# Buggy_Motor_Board.net
KiCad netlist of a schematic drawn in EAGLE
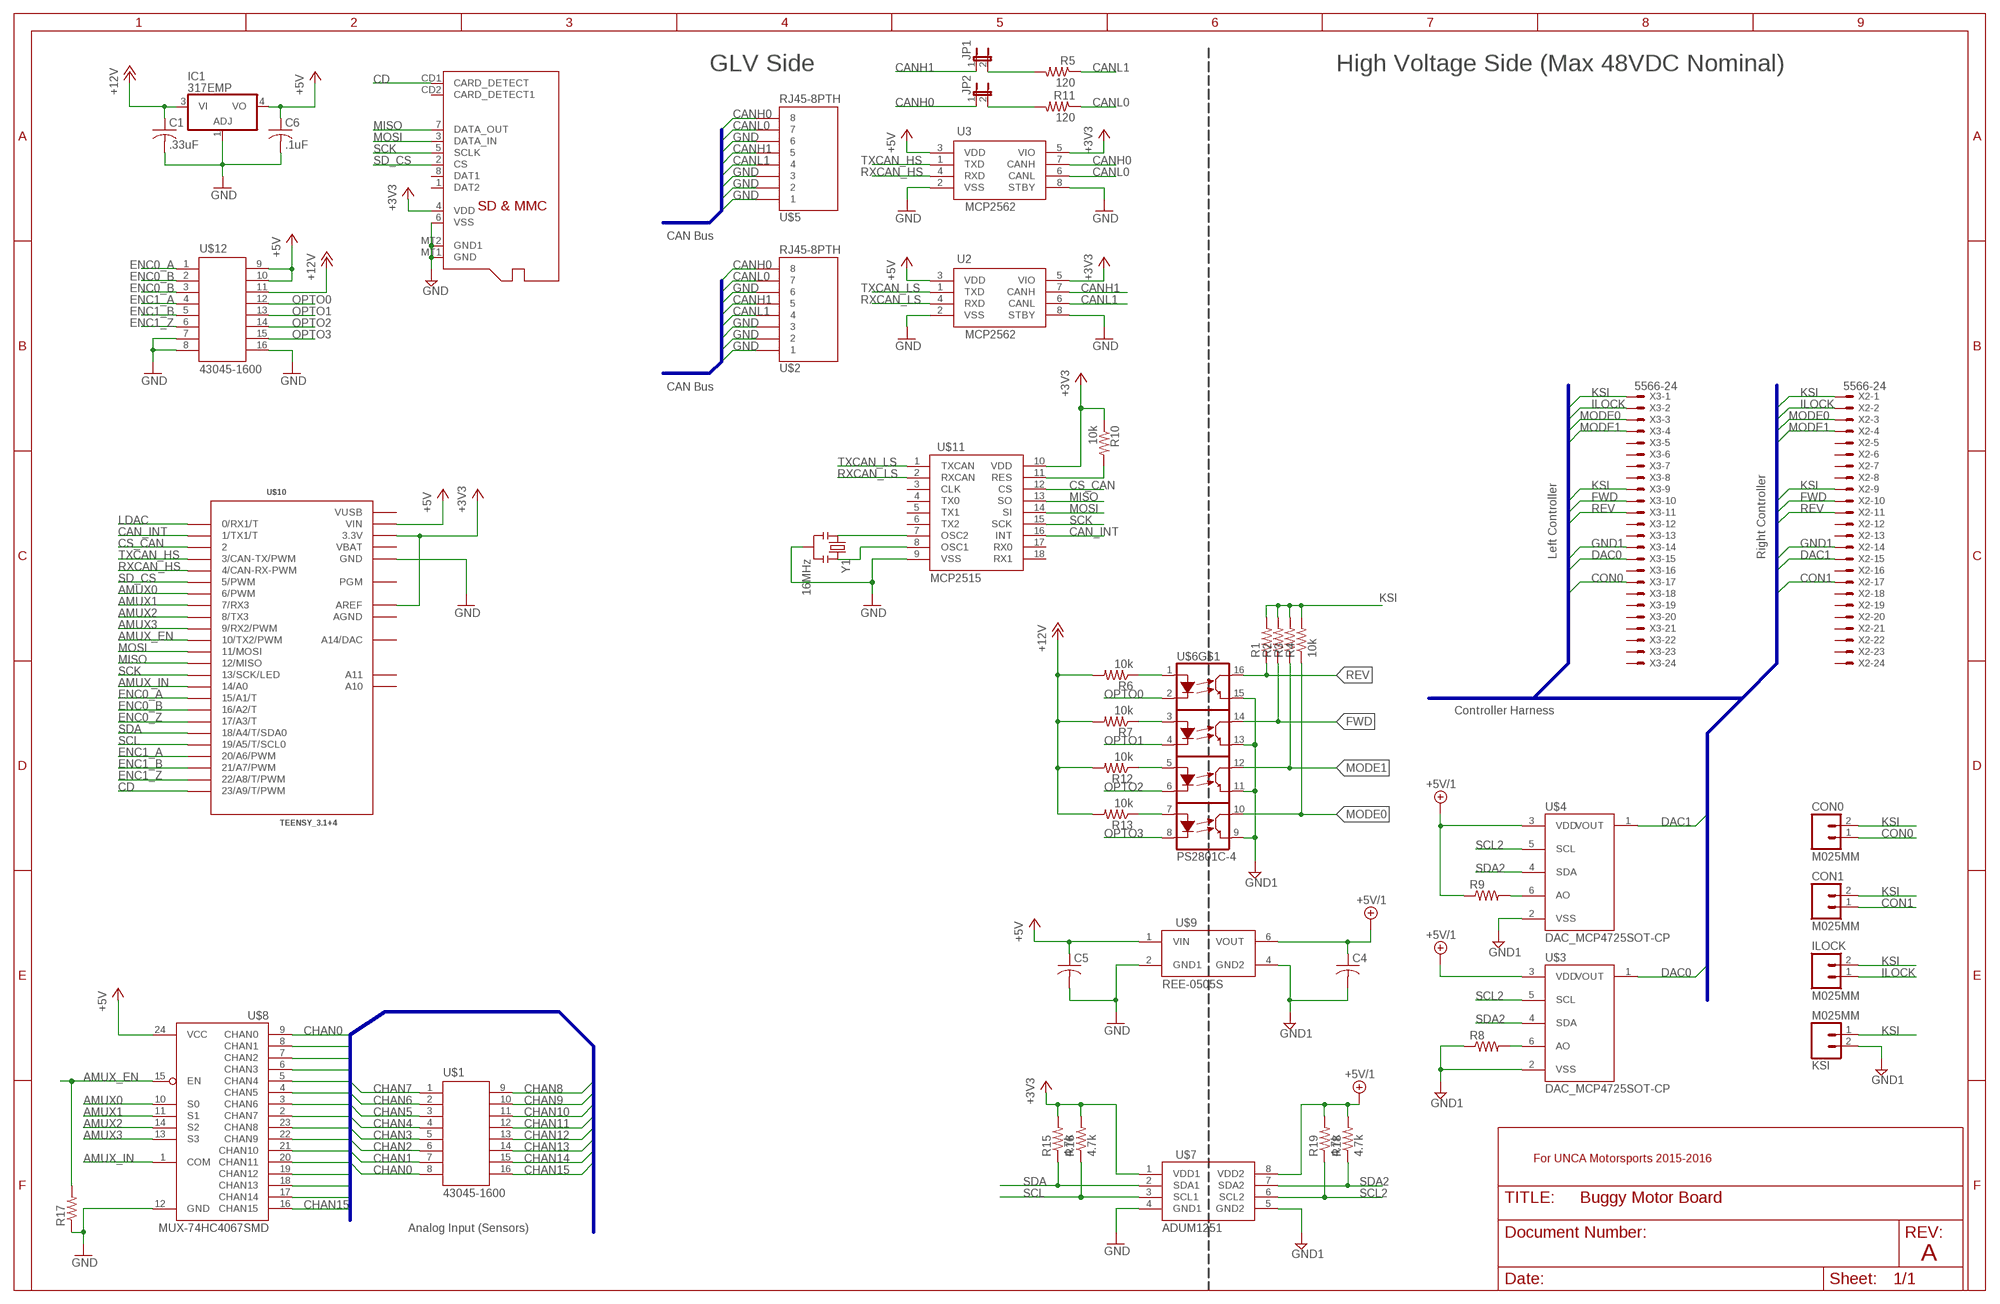
[diagram p0: schematic, sheet 1]

(export (version "E")
  (design (tool "Eeschema 10.0.6"))
  (components
    (comp (ref "C1")
      (value ".33uF")
      (footprint "eagle-import:C0805")
      (libsource (lib "eagle-import") (part "C-USC0805"))
    )
    (comp (ref "C4")
      (value "C-USC1210K")
      (footprint "eagle-import:C1210K")
      (libsource (lib "eagle-import") (part "C-USC1210K"))
    )
    (comp (ref "C5")
      (value "C-USC1210K")
      (footprint "eagle-import:C1210K")
      (libsource (lib "eagle-import") (part "C-USC1210K"))
    )
    (comp (ref "C6")
      (value ".1uF")
      (footprint "eagle-import:C0805")
      (libsource (lib "eagle-import") (part "C-USC0805"))
    )
    (comp (ref "CON0")
      (value "M025MM")
      (footprint "eagle-import:SCREWTERMINAL-5MM-2")
      (libsource (lib "eagle-import") (part "M025MM"))
    )
    (comp (ref "CON1")
      (value "M025MM")
      (footprint "eagle-import:SCREWTERMINAL-5MM-2")
      (libsource (lib "eagle-import") (part "M025MM"))
    )
    (comp (ref "IC1")
      (value "317EMP")
      (footprint "eagle-import:SOT223")
      (libsource (lib "eagle-import") (part "317EMP"))
    )
    (comp (ref "ILOCK")
      (value "M025MM")
      (footprint "eagle-import:SCREWTERMINAL-5MM-2")
      (libsource (lib "eagle-import") (part "M025MM"))
    )
    (comp (ref "JP1")
      (value "JP1E")
      (footprint "eagle-import:JP1")
      (libsource (lib "eagle-import") (part "JP1E"))
    )
    (comp (ref "JP2")
      (value "JP1E")
      (footprint "eagle-import:JP1")
      (libsource (lib "eagle-import") (part "JP1E"))
    )
    (comp (ref "KSI")
      (value "M025MM")
      (footprint "eagle-import:SCREWTERMINAL-5MM-2")
      (libsource (lib "eagle-import") (part "M025MM"))
    )
    (comp (ref "R1")
      (value "RESISTOR0805-RES")
      (footprint "eagle-import:0805")
      (libsource (lib "eagle-import") (part "RESISTOR0805-RES"))
    )
    (comp (ref "R2")
      (value "RESISTOR0805-RES")
      (footprint "eagle-import:0805")
      (libsource (lib "eagle-import") (part "RESISTOR0805-RES"))
    )
    (comp (ref "R3")
      (value "RESISTOR0805-RES")
      (footprint "eagle-import:0805")
      (libsource (lib "eagle-import") (part "RESISTOR0805-RES"))
    )
    (comp (ref "R4")
      (value "10k")
      (footprint "eagle-import:0805")
      (libsource (lib "eagle-import") (part "RESISTOR0805-RES"))
    )
    (comp (ref "R5")
      (value "120")
      (footprint "eagle-import:0805")
      (libsource (lib "eagle-import") (part "RESISTOR0805-RES"))
    )
    (comp (ref "R6")
      (value "10k")
      (footprint "eagle-import:0805")
      (libsource (lib "eagle-import") (part "RESISTOR0805-RES"))
    )
    (comp (ref "R7")
      (value "10k")
      (footprint "eagle-import:0805")
      (libsource (lib "eagle-import") (part "RESISTOR0805-RES"))
    )
    (comp (ref "R8")
      (value "RESISTOR0805-RES")
      (footprint "eagle-import:0805")
      (libsource (lib "eagle-import") (part "RESISTOR0805-RES"))
    )
    (comp (ref "R9")
      (value "RESISTOR0805-RES")
      (footprint "eagle-import:0805")
      (libsource (lib "eagle-import") (part "RESISTOR0805-RES"))
    )
    (comp (ref "R10")
      (value "10k")
      (footprint "eagle-import:0805")
      (libsource (lib "eagle-import") (part "RESISTOR0805-RES"))
    )
    (comp (ref "R11")
      (value "120")
      (footprint "eagle-import:0805")
      (libsource (lib "eagle-import") (part "RESISTOR0805-RES"))
    )
    (comp (ref "R12")
      (value "10k")
      (footprint "eagle-import:0805")
      (libsource (lib "eagle-import") (part "RESISTOR0805-RES"))
    )
    (comp (ref "R13")
      (value "10k")
      (footprint "eagle-import:0805")
      (libsource (lib "eagle-import") (part "RESISTOR0805-RES"))
    )
    (comp (ref "R15")
      (value "4.7k")
      (footprint "eagle-import:0805")
      (libsource (lib "eagle-import") (part "RESISTOR0805-RES"))
    )
    (comp (ref "R16")
      (value "4.7k")
      (footprint "eagle-import:0805")
      (libsource (lib "eagle-import") (part "RESISTOR0805-RES"))
    )
    (comp (ref "R17")
      (value "RESISTOR0805-RES")
      (footprint "eagle-import:0805")
      (libsource (lib "eagle-import") (part "RESISTOR0805-RES"))
    )
    (comp (ref "R18")
      (value "4.7k")
      (footprint "eagle-import:0805")
      (libsource (lib "eagle-import") (part "RESISTOR0805-RES"))
    )
    (comp (ref "R19")
      (value "4.7k")
      (footprint "eagle-import:0805")
      (libsource (lib "eagle-import") (part "RESISTOR0805-RES"))
    )
    (comp (ref "U$1")
      (value "43045-1600")
      (footprint "eagle-import:43045-1600")
      (libsource (lib "eagle-import") (part "43045-1600"))
    )
    (comp (ref "U$2")
      (value "RJ45-8PTH")
      (footprint "eagle-import:RJ45-8")
      (libsource (lib "eagle-import") (part "RJ45-8PTH"))
    )
    (comp (ref "U$3")
      (value "DAC_MCP4725SOT-CP")
      (footprint "eagle-import:SOT23-6-MCP4725")
      (libsource (lib "eagle-import") (part "DAC_MCP4725SOT-CP"))
    )
    (comp (ref "U$4")
      (value "DAC_MCP4725SOT-CP")
      (footprint "eagle-import:SOT23-6-MCP4725")
      (libsource (lib "eagle-import") (part "DAC_MCP4725SOT-CP"))
    )
    (comp (ref "U$5")
      (value "RJ45-8PTH")
      (footprint "eagle-import:RJ45-8")
      (libsource (lib "eagle-import") (part "RJ45-8PTH"))
    )
    (comp (ref "U$6")
      (value "PS2801C-4")
      (footprint "eagle-import:16-SOIC")
      (libsource (lib "eagle-import") (part "PS2801C-4"))
    )
    (comp (ref "U$7")
      (value "ADUM1251")
      (footprint "eagle-import:8-SOIC")
      (libsource (lib "eagle-import") (part "ADUM1251"))
    )
    (comp (ref "U$8")
      (value "MUX-74HC4067SMD")
      (footprint "eagle-import:SSOP24")
      (libsource (lib "eagle-import") (part "MUX-74HC4067SMD"))
    )
    (comp (ref "U$9")
      (value "REE-0505S")
      (footprint "eagle-import:REE-0505S")
      (libsource (lib "eagle-import") (part "REE-0505S"))
    )
    (comp (ref "U$10")
      (value "TEENSY_3.1+4")
      (footprint "eagle-import:TEENSY_3.1+4")
      (libsource (lib "eagle-import") (part "TEENSY_3.1+4"))
    )
    (comp (ref "U$11")
      (value "MCP2515")
      (footprint "eagle-import:DIL18")
      (libsource (lib "eagle-import") (part "MCP2515"))
    )
    (comp (ref "U$12")
      (value "43045-1600")
      (footprint "eagle-import:43045-1600")
      (libsource (lib "eagle-import") (part "43045-1600"))
    )
    (comp (ref "U2")
      (value "MCP2562")
      (footprint "eagle-import:SO08")
      (libsource (lib "eagle-import") (part "MCP2562"))
    )
    (comp (ref "U3")
      (value "MCP2562")
      (footprint "eagle-import:SO08")
      (libsource (lib "eagle-import") (part "MCP2562"))
    )
    (comp (ref "X1")
      (value "MICROSD")
      (footprint "eagle-import:MICROSD")
      (libsource (lib "eagle-import") (part "MICROSD"))
    )
    (comp (ref "X2")
      (value "5566-24")
      (footprint "eagle-import:5566-24")
      (libsource (lib "eagle-import") (part "5566-24"))
    )
    (comp (ref "X3")
      (value "5566-24")
      (footprint "eagle-import:5566-24")
      (libsource (lib "eagle-import") (part "5566-24"))
    )
    (comp (ref "Y1")
      (value "16MHz")
      (footprint "eagle-import:RESONATOR-PTH")
      (libsource (lib "eagle-import") (part "RESONATORPTH"))
    )
  )
  (nets
    (net (code "5") (name "+3V3") (class "Default")
      (node (ref "R10") (pin "1") (pinfunction "1_1") (pintype "passive"))
      (node (ref "R15") (pin "2") (pinfunction "2_2") (pintype "passive"))
      (node (ref "R16") (pin "2") (pinfunction "2_2") (pintype "passive"))
      (node (ref "U$10") (pin "3.3V") (pinfunction "3.3V_3.3V") (pintype "power_in"))
      (node (ref "U$10") (pin "3.3V1") (pinfunction "3.3V_3.3V1") (pintype "power_in"))
      (node (ref "U$10") (pin "AREF") (pinfunction "AREF_AREF") (pintype "power_in"))
      (node (ref "U$11") (pin "10") (pinfunction "VDD_10") (pintype "bidirectional"))
      (node (ref "U$7") (pin "1") (pinfunction "VDD1_1") (pintype "bidirectional"))
      (node (ref "U2") (pin "5") (pinfunction "VIO_5") (pintype "bidirectional"))
      (node (ref "U3") (pin "5") (pinfunction "VIO_5") (pintype "bidirectional"))
      (node (ref "X1") (pin "4") (pinfunction "VDD_4") (pintype "power_in"))
    )
    (net (code "6") (name "+5V") (class "Default")
      (node (ref "C5") (pin "1") (pinfunction "1_1") (pintype "passive"))
      (node (ref "C6") (pin "1") (pinfunction "1_1") (pintype "passive"))
      (node (ref "IC1") (pin "4") (pinfunction "VO_4") (pintype "passive"))
      (node (ref "U$10") (pin "VIN") (pinfunction "VIN_VIN") (pintype "power_in"))
      (node (ref "U$12") (pin "10") (pinfunction "P$10_10") (pintype "passive"))
      (node (ref "U$12") (pin "9") (pinfunction "P$9_9") (pintype "passive"))
      (node (ref "U$8") (pin "24") (pinfunction "VCC_24") (pintype "bidirectional"))
      (node (ref "U$9") (pin "1") (pinfunction "VIN_1") (pintype "bidirectional"))
      (node (ref "U2") (pin "3") (pinfunction "VDD_3") (pintype "bidirectional"))
      (node (ref "U3") (pin "3") (pinfunction "VDD_3") (pintype "bidirectional"))
    )
    (net (code "7") (name "+5V{slash}1") (class "Default")
      (node (ref "C4") (pin "1") (pinfunction "1_1") (pintype "passive"))
      (node (ref "R18") (pin "2") (pinfunction "2_2") (pintype "passive"))
      (node (ref "R19") (pin "2") (pinfunction "2_2") (pintype "passive"))
      (node (ref "R9") (pin "1") (pinfunction "1_1") (pintype "passive"))
      (node (ref "U$3") (pin "3") (pinfunction "VDD_3") (pintype "bidirectional"))
      (node (ref "U$4") (pin "3") (pinfunction "VDD_3") (pintype "bidirectional"))
      (node (ref "U$7") (pin "8") (pinfunction "VDD2_8") (pintype "bidirectional"))
      (node (ref "U$9") (pin "6") (pinfunction "VOUT_6") (pintype "bidirectional"))
    )
    (net (code "8") (name "+12V") (class "Default")
      (node (ref "C1") (pin "1") (pinfunction "1_1") (pintype "passive"))
      (node (ref "IC1") (pin "3") (pinfunction "VI_3") (pintype "input"))
      (node (ref "R12") (pin "2") (pinfunction "2_2") (pintype "passive"))
      (node (ref "R13") (pin "2") (pinfunction "2_2") (pintype "passive"))
      (node (ref "R6") (pin "2") (pinfunction "2_2") (pintype "passive"))
      (node (ref "R7") (pin "2") (pinfunction "2_2") (pintype "passive"))
      (node (ref "U$12") (pin "11") (pinfunction "P$11_11") (pintype "passive"))
    )
    (net (code "9") (name "/AGND") (class "Default")
      (node (ref "U$10") (pin "AGND") (pinfunction "AGND_AGND") (pintype "power_in"))
    )
    (net (code "10") (name "/AMUX0") (class "Default")
      (node (ref "U$10") (pin "6") (pinfunction "6/PWM_6") (pintype "bidirectional"))
      (node (ref "U$8") (pin "10") (pinfunction "S0_10") (pintype "input"))
    )
    (net (code "11") (name "/AMUX1") (class "Default")
      (node (ref "U$10") (pin "7") (pinfunction "7/RX3_7") (pintype "bidirectional"))
      (node (ref "U$8") (pin "11") (pinfunction "S1_11") (pintype "input"))
    )
    (net (code "12") (name "/AMUX2") (class "Default")
      (node (ref "U$10") (pin "8") (pinfunction "8/TX3_8") (pintype "bidirectional"))
      (node (ref "U$8") (pin "14") (pinfunction "S2_14") (pintype "input"))
    )
    (net (code "13") (name "/AMUX3") (class "Default")
      (node (ref "U$10") (pin "9") (pinfunction "9/RX2/PWM_9") (pintype "bidirectional"))
      (node (ref "U$8") (pin "13") (pinfunction "S3_13") (pintype "input"))
    )
    (net (code "14") (name "/AMUX_EN") (class "Default")
      (node (ref "R17") (pin "2") (pinfunction "2_2") (pintype "passive"))
      (node (ref "U$10") (pin "10") (pinfunction "10/TX2/PWM_10") (pintype "bidirectional"))
      (node (ref "U$8") (pin "15") (pinfunction "EN_15") (pintype "input"))
    )
    (net (code "15") (name "/AMUX_IN") (class "Default")
      (node (ref "U$10") (pin "14/A0") (pinfunction "14/A0_14/A0") (pintype "bidirectional"))
      (node (ref "U$8") (pin "1") (pinfunction "COM_1") (pintype "bidirectional"))
    )
    (net (code "16") (name "/CANH0") (class "Default")
      (node (ref "JP2") (pin "1") (pinfunction "1_1") (pintype "passive"))
      (node (ref "U$2") (pin "8") (pinfunction "8_8") (pintype "bidirectional"))
      (node (ref "U$5") (pin "8") (pinfunction "8_8") (pintype "bidirectional"))
      (node (ref "U3") (pin "7") (pinfunction "CANH_7") (pintype "bidirectional"))
    )
    (net (code "17") (name "/CANH1") (class "Default")
      (node (ref "JP1") (pin "1") (pinfunction "1_1") (pintype "passive"))
      (node (ref "U$2") (pin "5") (pinfunction "5_5") (pintype "bidirectional"))
      (node (ref "U$5") (pin "5") (pinfunction "5_5") (pintype "bidirectional"))
      (node (ref "U2") (pin "7") (pinfunction "CANH_7") (pintype "bidirectional"))
    )
    (net (code "18") (name "/CANL0") (class "Default")
      (node (ref "R11") (pin "1") (pinfunction "1_1") (pintype "passive"))
      (node (ref "U$2") (pin "7") (pinfunction "7_7") (pintype "bidirectional"))
      (node (ref "U$5") (pin "7") (pinfunction "7_7") (pintype "bidirectional"))
      (node (ref "U3") (pin "6") (pinfunction "CANL_6") (pintype "bidirectional"))
    )
    (net (code "19") (name "/CANL1") (class "Default")
      (node (ref "R5") (pin "1") (pinfunction "1_1") (pintype "passive"))
      (node (ref "U$2") (pin "4") (pinfunction "4_4") (pintype "bidirectional"))
      (node (ref "U$5") (pin "4") (pinfunction "4_4") (pintype "bidirectional"))
      (node (ref "U2") (pin "6") (pinfunction "CANL_6") (pintype "bidirectional"))
    )
    (net (code "20") (name "/CAN_INT") (class "Default")
      (node (ref "U$10") (pin "1") (pinfunction "1/TX1/T_1") (pintype "bidirectional"))
      (node (ref "U$11") (pin "16") (pinfunction "INT_16") (pintype "bidirectional"))
    )
    (net (code "21") (name "/CD") (class "Default")
      (node (ref "U$10") (pin "23/A9") (pinfunction "23/A9/T/PWM_23/A9") (pintype "bidirectional"))
      (node (ref "X1") (pin "CD1") (pinfunction "CARD_DETECT_CD1") (pintype "passive"))
    )
    (net (code "22") (name "/CHAN0") (class "Default")
      (node (ref "U$1") (pin "8") (pinfunction "P$8_8") (pintype "passive"))
      (node (ref "U$8") (pin "9") (pinfunction "CHAN0_9") (pintype "bidirectional"))
    )
    (net (code "23") (name "/CHAN1") (class "Default")
      (node (ref "U$1") (pin "7") (pinfunction "P$7_7") (pintype "passive"))
      (node (ref "U$8") (pin "8") (pinfunction "CHAN1_8") (pintype "bidirectional"))
    )
    (net (code "24") (name "/CHAN2") (class "Default")
      (node (ref "U$1") (pin "6") (pinfunction "P$6_6") (pintype "passive"))
      (node (ref "U$8") (pin "7") (pinfunction "CHAN2_7") (pintype "bidirectional"))
    )
    (net (code "25") (name "/CHAN3") (class "Default")
      (node (ref "U$1") (pin "5") (pinfunction "P$5_5") (pintype "passive"))
      (node (ref "U$8") (pin "6") (pinfunction "CHAN3_6") (pintype "bidirectional"))
    )
    (net (code "26") (name "/CHAN4") (class "Default")
      (node (ref "U$1") (pin "4") (pinfunction "P$4_4") (pintype "passive"))
      (node (ref "U$8") (pin "5") (pinfunction "CHAN4_5") (pintype "bidirectional"))
    )
    (net (code "27") (name "/CHAN5") (class "Default")
      (node (ref "U$1") (pin "3") (pinfunction "P$3_3") (pintype "passive"))
      (node (ref "U$8") (pin "4") (pinfunction "CHAN5_4") (pintype "bidirectional"))
    )
    (net (code "28") (name "/CHAN6") (class "Default")
      (node (ref "U$1") (pin "2") (pinfunction "P$2_2") (pintype "passive"))
      (node (ref "U$8") (pin "3") (pinfunction "CHAN6_3") (pintype "bidirectional"))
    )
    (net (code "29") (name "/CHAN7") (class "Default")
      (node (ref "U$1") (pin "1") (pinfunction "P$1_1") (pintype "passive"))
      (node (ref "U$8") (pin "2") (pinfunction "CHAN7_2") (pintype "bidirectional"))
    )
    (net (code "30") (name "/CHAN8") (class "Default")
      (node (ref "U$1") (pin "9") (pinfunction "P$9_9") (pintype "passive"))
      (node (ref "U$8") (pin "23") (pinfunction "CHAN8_23") (pintype "bidirectional"))
    )
    (net (code "31") (name "/CHAN9") (class "Default")
      (node (ref "U$1") (pin "10") (pinfunction "P$10_10") (pintype "passive"))
      (node (ref "U$8") (pin "22") (pinfunction "CHAN9_22") (pintype "bidirectional"))
    )
    (net (code "32") (name "/CHAN10") (class "Default")
      (node (ref "U$1") (pin "11") (pinfunction "P$11_11") (pintype "passive"))
      (node (ref "U$8") (pin "21") (pinfunction "CHAN10_21") (pintype "bidirectional"))
    )
    (net (code "33") (name "/CHAN11") (class "Default")
      (node (ref "U$1") (pin "12") (pinfunction "P$12_12") (pintype "passive"))
      (node (ref "U$8") (pin "20") (pinfunction "CHAN11_20") (pintype "bidirectional"))
    )
    (net (code "34") (name "/CHAN12") (class "Default")
      (node (ref "U$1") (pin "13") (pinfunction "P$13_13") (pintype "passive"))
      (node (ref "U$8") (pin "19") (pinfunction "CHAN12_19") (pintype "bidirectional"))
    )
    (net (code "35") (name "/CHAN13") (class "Default")
      (node (ref "U$1") (pin "14") (pinfunction "P$14_14") (pintype "passive"))
      (node (ref "U$8") (pin "18") (pinfunction "CHAN13_18") (pintype "bidirectional"))
    )
    (net (code "36") (name "/CHAN14") (class "Default")
      (node (ref "U$1") (pin "15") (pinfunction "P$15_15") (pintype "passive"))
      (node (ref "U$8") (pin "17") (pinfunction "CHAN14_17") (pintype "bidirectional"))
    )
    (net (code "37") (name "/CHAN15") (class "Default")
      (node (ref "U$1") (pin "16") (pinfunction "P$16_16") (pintype "passive"))
      (node (ref "U$8") (pin "16") (pinfunction "CHAN15_16") (pintype "bidirectional"))
    )
    (net (code "38") (name "/CON0") (class "Default")
      (node (ref "CON0") (pin "1") (pinfunction "1_1") (pintype "passive"))
      (node (ref "X3") (pin "17") (pinfunction "S_17") (pintype "passive"))
    )
    (net (code "39") (name "/CON1") (class "Default")
      (node (ref "CON1") (pin "1") (pinfunction "1_1") (pintype "passive"))
      (node (ref "X2") (pin "17") (pinfunction "S_17") (pintype "passive"))
    )
    (net (code "40") (name "/CS_CAN") (class "Default")
      (node (ref "U$10") (pin "2") (pinfunction "2_2") (pintype "bidirectional"))
      (node (ref "U$11") (pin "12") (pinfunction "CS_12") (pintype "bidirectional"))
    )
    (net (code "41") (name "/DAC0") (class "Default")
      (node (ref "U$3") (pin "1") (pinfunction "VOUT_1") (pintype "bidirectional"))
      (node (ref "X3") (pin "15") (pinfunction "S_15") (pintype "passive"))
    )
    (net (code "42") (name "/DAC1") (class "Default")
      (node (ref "U$4") (pin "1") (pinfunction "VOUT_1") (pintype "bidirectional"))
      (node (ref "X2") (pin "15") (pinfunction "S_15") (pintype "passive"))
    )
    (net (code "43") (name "/ENC0_A") (class "Default")
      (node (ref "U$10") (pin "15/A1") (pinfunction "15/A1/T_15/A1") (pintype "bidirectional"))
      (node (ref "U$12") (pin "1") (pinfunction "P$1_1") (pintype "passive"))
    )
    (net (code "44") (name "/ENC0_B") (class "Default")
      (node (ref "U$10") (pin "16/A2") (pinfunction "16/A2/T_16/A2") (pintype "bidirectional"))
      (node (ref "U$12") (pin "2") (pinfunction "P$2_2") (pintype "passive"))
    )
    (net (code "45") (name "/ENC0_Z") (class "Default")
      (node (ref "U$10") (pin "17/A3") (pinfunction "17/A3/T_17/A3") (pintype "bidirectional"))
      (node (ref "U$12") (pin "3") (pinfunction "P$3_3") (pintype "passive"))
    )
    (net (code "46") (name "/ENC1_A") (class "Default")
      (node (ref "U$10") (pin "20/A6") (pinfunction "20/A6/PWM_20/A6") (pintype "bidirectional"))
      (node (ref "U$12") (pin "4") (pinfunction "P$4_4") (pintype "passive"))
    )
    (net (code "47") (name "/ENC1_B") (class "Default")
      (node (ref "U$10") (pin "21/A7") (pinfunction "21/A7/PWM_21/A7") (pintype "bidirectional"))
      (node (ref "U$12") (pin "5") (pinfunction "P$5_5") (pintype "passive"))
    )
    (net (code "48") (name "/ENC1_Z") (class "Default")
      (node (ref "U$10") (pin "22/A8") (pinfunction "22/A8/T/PWM_22/A8") (pintype "bidirectional"))
      (node (ref "U$12") (pin "6") (pinfunction "P$6_6") (pintype "passive"))
    )
    (net (code "49") (name "/ILOCK") (class "Default")
      (node (ref "ILOCK") (pin "1") (pinfunction "1_1") (pintype "passive"))
      (node (ref "X2") (pin "2") (pinfunction "S_2") (pintype "passive"))
      (node (ref "X3") (pin "2") (pinfunction "S_2") (pintype "passive"))
    )
    (net (code "50") (name "/KSI") (class "Default")
      (node (ref "CON0") (pin "2") (pinfunction "2_2") (pintype "passive"))
      (node (ref "CON1") (pin "2") (pinfunction "2_2") (pintype "passive"))
      (node (ref "ILOCK") (pin "2") (pinfunction "2_2") (pintype "passive"))
      (node (ref "KSI") (pin "1") (pinfunction "1_1") (pintype "passive"))
      (node (ref "R1") (pin "2") (pinfunction "2_2") (pintype "passive"))
      (node (ref "R2") (pin "2") (pinfunction "2_2") (pintype "passive"))
      (node (ref "R3") (pin "2") (pinfunction "2_2") (pintype "passive"))
      (node (ref "R4") (pin "2") (pinfunction "2_2") (pintype "passive"))
      (node (ref "X2") (pin "1") (pinfunction "S_1") (pintype "passive"))
      (node (ref "X2") (pin "9") (pinfunction "S_9") (pintype "passive"))
      (node (ref "X3") (pin "1") (pinfunction "S_1") (pintype "passive"))
      (node (ref "X3") (pin "9") (pinfunction "S_9") (pintype "passive"))
    )
    (net (code "51") (name "/LDAC") (class "Default")
      (node (ref "U$10") (pin "0") (pinfunction "0/RX1/T_0") (pintype "bidirectional"))
    )
    (net (code "52") (name "/MISO") (class "Default")
      (node (ref "U$10") (pin "12") (pinfunction "12/MISO_12") (pintype "bidirectional"))
      (node (ref "U$11") (pin "13") (pinfunction "SO_13") (pintype "bidirectional"))
      (node (ref "X1") (pin "7") (pinfunction "DATA_OUT_7") (pintype "output"))
    )
    (net (code "53") (name "/MOSI") (class "Default")
      (node (ref "U$10") (pin "11") (pinfunction "11/MOSI_11") (pintype "bidirectional"))
      (node (ref "U$11") (pin "14") (pinfunction "SI_14") (pintype "bidirectional"))
      (node (ref "X1") (pin "3") (pinfunction "DATA_IN_3") (pintype "input"))
    )
    (net (code "54") (name "/OPTO0") (class "Default")
      (node (ref "U$12") (pin "12") (pinfunction "P$12_12") (pintype "passive"))
      (node (ref "U$6") (pin "2") (pinfunction "C_2") (pintype "passive"))
    )
    (net (code "55") (name "/OPTO1") (class "Default")
      (node (ref "U$12") (pin "13") (pinfunction "P$13_13") (pintype "passive"))
      (node (ref "U$6") (pin "4") (pinfunction "C_4") (pintype "passive"))
    )
    (net (code "56") (name "/OPTO2") (class "Default")
      (node (ref "U$12") (pin "14") (pinfunction "P$14_14") (pintype "passive"))
      (node (ref "U$6") (pin "6") (pinfunction "C_6") (pintype "passive"))
    )
    (net (code "57") (name "/OPTO3") (class "Default")
      (node (ref "U$12") (pin "15") (pinfunction "P$15_15") (pintype "passive"))
      (node (ref "U$6") (pin "8") (pinfunction "C_8") (pintype "passive"))
    )
    (net (code "58") (name "/RXCAN_HS") (class "Default")
      (node (ref "U$10") (pin "4") (pinfunction "4/CAN-RX-PWM_4") (pintype "bidirectional"))
      (node (ref "U3") (pin "4") (pinfunction "RXD_4") (pintype "bidirectional"))
    )
    (net (code "59") (name "/RXCAN_LS") (class "Default")
      (node (ref "U$11") (pin "2") (pinfunction "RXCAN_2") (pintype "bidirectional"))
      (node (ref "U2") (pin "4") (pinfunction "RXD_4") (pintype "bidirectional"))
    )
    (net (code "60") (name "/SCK") (class "Default")
      (node (ref "U$10") (pin "13") (pinfunction "13/SCK/LED_13") (pintype "bidirectional"))
      (node (ref "U$11") (pin "15") (pinfunction "SCK_15") (pintype "bidirectional"))
      (node (ref "X1") (pin "5") (pinfunction "SCLK_5") (pintype "input"))
    )
    (net (code "61") (name "/SCL") (class "Default")
      (node (ref "R16") (pin "1") (pinfunction "1_1") (pintype "passive"))
      (node (ref "U$10") (pin "19/A5") (pinfunction "19/A5/T/SCL0_19/A5") (pintype "bidirectional"))
      (node (ref "U$7") (pin "3") (pinfunction "SCL1_3") (pintype "bidirectional"))
    )
    (net (code "62") (name "/SCL2") (class "Default")
      (node (ref "R19") (pin "1") (pinfunction "1_1") (pintype "passive"))
      (node (ref "U$3") (pin "5") (pinfunction "SCL_5") (pintype "bidirectional"))
      (node (ref "U$4") (pin "5") (pinfunction "SCL_5") (pintype "bidirectional"))
      (node (ref "U$7") (pin "6") (pinfunction "SCL2_6") (pintype "bidirectional"))
    )
    (net (code "63") (name "/SDA") (class "Default")
      (node (ref "R15") (pin "1") (pinfunction "1_1") (pintype "passive"))
      (node (ref "U$10") (pin "18/A4") (pinfunction "18/A4/T/SDA0_18/A4") (pintype "bidirectional"))
      (node (ref "U$7") (pin "2") (pinfunction "SDA1_2") (pintype "bidirectional"))
    )
    (net (code "64") (name "/SDA2") (class "Default")
      (node (ref "R18") (pin "1") (pinfunction "1_1") (pintype "passive"))
      (node (ref "U$3") (pin "4") (pinfunction "SDA_4") (pintype "bidirectional"))
      (node (ref "U$4") (pin "4") (pinfunction "SDA_4") (pintype "bidirectional"))
      (node (ref "U$7") (pin "7") (pinfunction "SDA2_7") (pintype "bidirectional"))
    )
    (net (code "65") (name "/SD_CS") (class "Default")
      (node (ref "U$10") (pin "5") (pinfunction "5/PWM_5") (pintype "bidirectional"))
      (node (ref "X1") (pin "2") (pinfunction "CS_2") (pintype "input"))
    )
    (net (code "66") (name "/TXCAN_HS") (class "Default")
      (node (ref "U$10") (pin "3") (pinfunction "3/CAN-TX/PWM_3") (pintype "bidirectional"))
      (node (ref "U3") (pin "1") (pinfunction "TXD_1") (pintype "bidirectional"))
    )
    (net (code "67") (name "/TXCAN_LS") (class "Default")
      (node (ref "U$11") (pin "1") (pinfunction "TXCAN_1") (pintype "bidirectional"))
      (node (ref "U2") (pin "1") (pinfunction "TXD_1") (pintype "bidirectional"))
    )
    (net (code "68") (name "/VBAT") (class "Default")
      (node (ref "U$10") (pin "VBAT") (pinfunction "VBAT_VBAT") (pintype "power_in"))
    )
    (net (code "69") (name "/VUSB") (class "Default")
      (node (ref "U$10") (pin "VUSB") (pinfunction "VUSB_VUSB") (pintype "power_in"))
    )
    (net (code "71") (name "FWD") (class "Default")
      (node (ref "R2") (pin "1") (pinfunction "1_1") (pintype "passive"))
      (node (ref "U$6") (pin "14") (pinfunction "L1_14") (pintype "passive"))
      (node (ref "X2") (pin "10") (pinfunction "S_10") (pintype "passive"))
      (node (ref "X3") (pin "10") (pinfunction "S_10") (pintype "passive"))
    )
    (net (code "72") (name "GND") (class "Default")
      (node (ref "C1") (pin "2") (pinfunction "2_2") (pintype "passive"))
      (node (ref "C5") (pin "2") (pinfunction "2_2") (pintype "passive"))
      (node (ref "C6") (pin "2") (pinfunction "2_2") (pintype "passive"))
      (node (ref "IC1") (pin "1") (pinfunction "ADJ_1") (pintype "input"))
      (node (ref "R17") (pin "1") (pinfunction "1_1") (pintype "passive"))
      (node (ref "U$10") (pin "GND") (pinfunction "GND_GND") (pintype "power_in"))
      (node (ref "U$10") (pin "GND1") (pinfunction "GND_GND1") (pintype "power_in"))
      (node (ref "U$11") (pin "9") (pinfunction "VSS_9") (pintype "bidirectional"))
      (node (ref "U$12") (pin "16") (pinfunction "P$16_16") (pintype "passive"))
      (node (ref "U$12") (pin "7") (pinfunction "P$7_7") (pintype "passive"))
      (node (ref "U$12") (pin "8") (pinfunction "P$8_8") (pintype "passive"))
      (node (ref "U$2") (pin "1") (pinfunction "1_1") (pintype "bidirectional"))
      (node (ref "U$2") (pin "2") (pinfunction "2_2") (pintype "bidirectional"))
      (node (ref "U$2") (pin "3") (pinfunction "3_3") (pintype "bidirectional"))
      (node (ref "U$2") (pin "6") (pinfunction "6_6") (pintype "bidirectional"))
      (node (ref "U$5") (pin "1") (pinfunction "1_1") (pintype "bidirectional"))
      (node (ref "U$5") (pin "2") (pinfunction "2_2") (pintype "bidirectional"))
      (node (ref "U$5") (pin "3") (pinfunction "3_3") (pintype "bidirectional"))
      (node (ref "U$5") (pin "6") (pinfunction "6_6") (pintype "bidirectional"))
      (node (ref "U$7") (pin "4") (pinfunction "GND1_4") (pintype "bidirectional"))
      (node (ref "U$8") (pin "12") (pinfunction "GND_12") (pintype "bidirectional"))
      (node (ref "U$9") (pin "2") (pinfunction "GND1_2") (pintype "bidirectional"))
      (node (ref "U2") (pin "2") (pinfunction "VSS_2") (pintype "bidirectional"))
      (node (ref "U2") (pin "8") (pinfunction "STBY_8") (pintype "bidirectional"))
      (node (ref "U3") (pin "2") (pinfunction "VSS_2") (pintype "bidirectional"))
      (node (ref "U3") (pin "8") (pinfunction "STBY_8") (pintype "bidirectional"))
      (node (ref "X1") (pin "6") (pinfunction "VSS_6") (pintype "power_in"))
      (node (ref "X1") (pin "MT1") (pinfunction "GND_MT1") (pintype "power_in"))
      (node (ref "X1") (pin "MT2") (pinfunction "GND1_MT2") (pintype "power_in"))
      (node (ref "Y1") (pin "2") (pinfunction "2_2") (pintype "passive"))
    )
    (net (code "73") (name "GND1") (class "Default")
      (node (ref "C4") (pin "2") (pinfunction "2_2") (pintype "passive"))
      (node (ref "KSI") (pin "2") (pinfunction "2_2") (pintype "passive"))
      (node (ref "R8") (pin "1") (pinfunction "1_1") (pintype "passive"))
      (node (ref "U$3") (pin "2") (pinfunction "VSS_2") (pintype "bidirectional"))
      (node (ref "U$4") (pin "2") (pinfunction "VSS_2") (pintype "bidirectional"))
      (node (ref "U$6") (pin "11") (pinfunction "L2_11") (pintype "passive"))
      (node (ref "U$6") (pin "13") (pinfunction "L2_13") (pintype "passive"))
      (node (ref "U$6") (pin "15") (pinfunction "L2_15") (pintype "passive"))
      (node (ref "U$6") (pin "9") (pinfunction "L2_9") (pintype "passive"))
      (node (ref "U$7") (pin "5") (pinfunction "GND2_5") (pintype "bidirectional"))
      (node (ref "U$9") (pin "4") (pinfunction "GND2_4") (pintype "bidirectional"))
      (node (ref "X2") (pin "14") (pinfunction "S_14") (pintype "passive"))
      (node (ref "X3") (pin "14") (pinfunction "S_14") (pintype "passive"))
    )
    (net (code "74") (name "MODE0") (class "Default")
      (node (ref "R4") (pin "1") (pinfunction "1_1") (pintype "passive"))
      (node (ref "U$6") (pin "10") (pinfunction "L1_10") (pintype "passive"))
      (node (ref "X2") (pin "3") (pinfunction "S_3") (pintype "passive"))
      (node (ref "X3") (pin "3") (pinfunction "S_3") (pintype "passive"))
    )
    (net (code "75") (name "MODE1") (class "Default")
      (node (ref "R3") (pin "1") (pinfunction "1_1") (pintype "passive"))
      (node (ref "U$6") (pin "12") (pinfunction "L1_12") (pintype "passive"))
      (node (ref "X2") (pin "4") (pinfunction "S_4") (pintype "passive"))
      (node (ref "X3") (pin "4") (pinfunction "S_4") (pintype "passive"))
    )
    (net (code "76") (name "Net-(JP1-Pad2)") (class "Default")
      (node (ref "JP1") (pin "2") (pinfunction "2_2") (pintype "passive"))
      (node (ref "R5") (pin "2") (pinfunction "2_2") (pintype "passive"))
    )
    (net (code "77") (name "Net-(JP2-Pad2)") (class "Default")
      (node (ref "JP2") (pin "2") (pinfunction "2_2") (pintype "passive"))
      (node (ref "R11") (pin "2") (pinfunction "2_2") (pintype "passive"))
    )
    (net (code "78") (name "Net-(U$3-AO)") (class "Default")
      (node (ref "R8") (pin "2") (pinfunction "2_2") (pintype "passive"))
      (node (ref "U$3") (pin "6") (pinfunction "AO_6") (pintype "bidirectional"))
    )
    (net (code "79") (name "Net-(U$4-AO)") (class "Default")
      (node (ref "R9") (pin "2") (pinfunction "2_2") (pintype "passive"))
      (node (ref "U$4") (pin "6") (pinfunction "AO_6") (pintype "bidirectional"))
    )
    (net (code "80") (name "Net-(U$6A-A)") (class "Default")
      (node (ref "R6") (pin "1") (pinfunction "1_1") (pintype "passive"))
      (node (ref "U$6") (pin "1") (pinfunction "A_1") (pintype "passive"))
    )
    (net (code "81") (name "Net-(U$6B-A)") (class "Default")
      (node (ref "R7") (pin "1") (pinfunction "1_1") (pintype "passive"))
      (node (ref "U$6") (pin "3") (pinfunction "A_3") (pintype "passive"))
    )
    (net (code "82") (name "Net-(U$6C-A)") (class "Default")
      (node (ref "R12") (pin "1") (pinfunction "1_1") (pintype "passive"))
      (node (ref "U$6") (pin "5") (pinfunction "A_5") (pintype "passive"))
    )
    (net (code "83") (name "Net-(U$6D-A)") (class "Default")
      (node (ref "R13") (pin "1") (pinfunction "1_1") (pintype "passive"))
      (node (ref "U$6") (pin "7") (pinfunction "A_7") (pintype "passive"))
    )
    (net (code "84") (name "Net-(U$11-OSC1)") (class "Default")
      (node (ref "U$11") (pin "8") (pinfunction "OSC1_8") (pintype "bidirectional"))
      (node (ref "Y1") (pin "3") (pinfunction "3_3") (pintype "passive"))
    )
    (net (code "85") (name "Net-(U$11-OSC2)") (class "Default")
      (node (ref "U$11") (pin "7") (pinfunction "OSC2_7") (pintype "bidirectional"))
      (node (ref "Y1") (pin "1") (pinfunction "1_1") (pintype "passive"))
    )
    (net (code "86") (name "Net-(U$11-RES)") (class "Default")
      (node (ref "R10") (pin "2") (pinfunction "2_2") (pintype "passive"))
      (node (ref "U$11") (pin "11") (pinfunction "RES_11") (pintype "bidirectional"))
    )
    (net (code "87") (name "REV") (class "Default")
      (node (ref "R1") (pin "1") (pinfunction "1_1") (pintype "passive"))
      (node (ref "U$6") (pin "16") (pinfunction "L1_16") (pintype "passive"))
      (node (ref "X2") (pin "11") (pinfunction "S_11") (pintype "passive"))
      (node (ref "X3") (pin "11") (pinfunction "S_11") (pintype "passive"))
    )
    (net (code "88") (name "unconnected-(U$10-A14{slash}DAC-PadA14)") (class "Default")
      (node (ref "U$10") (pin "A14") (pinfunction "A14/DAC_A14") (pintype "bidirectional"))
    )
    (net (code "89") (name "unconnected-(U$10-PadA10)") (class "Default")
      (node (ref "U$10") (pin "A10") (pinfunction "A10_A10") (pintype "bidirectional"))
    )
    (net (code "90") (name "unconnected-(U$10-PadA11)") (class "Default")
      (node (ref "U$10") (pin "A11") (pinfunction "A11_A11") (pintype "bidirectional"))
    )
    (net (code "91") (name "unconnected-(U$10-PadPGM)") (class "Default")
      (node (ref "U$10") (pin "PGM") (pinfunction "PGM_PGM") (pintype "bidirectional"))
    )
    (net (code "92") (name "unconnected-(U$11-CLK-Pad3)") (class "Default")
      (node (ref "U$11") (pin "3") (pinfunction "CLK_3") (pintype "bidirectional"))
    )
    (net (code "93") (name "unconnected-(U$11-RX0-Pad17)") (class "Default")
      (node (ref "U$11") (pin "17") (pinfunction "RX0_17") (pintype "bidirectional"))
    )
    (net (code "94") (name "unconnected-(U$11-RX1-Pad18)") (class "Default")
      (node (ref "U$11") (pin "18") (pinfunction "RX1_18") (pintype "bidirectional"))
    )
    (net (code "95") (name "unconnected-(U$11-TX0-Pad4)") (class "Default")
      (node (ref "U$11") (pin "4") (pinfunction "TX0_4") (pintype "bidirectional"))
    )
    (net (code "96") (name "unconnected-(U$11-TX1-Pad5)") (class "Default")
      (node (ref "U$11") (pin "5") (pinfunction "TX1_5") (pintype "bidirectional"))
    )
    (net (code "97") (name "unconnected-(U$11-TX2-Pad6)") (class "Default")
      (node (ref "U$11") (pin "6") (pinfunction "TX2_6") (pintype "bidirectional"))
    )
    (net (code "98") (name "unconnected-(X1-CARD_DETECT1-PadCD2)") (class "Default")
      (node (ref "X1") (pin "CD2") (pinfunction "CARD_DETECT1_CD2") (pintype "passive"))
    )
    (net (code "99") (name "unconnected-(X1-DAT1-Pad8)") (class "Default")
      (node (ref "X1") (pin "8") (pinfunction "DAT1_8") (pintype "bidirectional"))
    )
    (net (code "100") (name "unconnected-(X1-DAT2-Pad1)") (class "Default")
      (node (ref "X1") (pin "1") (pinfunction "DAT2_1") (pintype "bidirectional"))
    )
    (net (code "101") (name "unconnected-(X2D-S-Pad12)") (class "Default")
      (node (ref "X2") (pin "12") (pinfunction "S_12") (pintype "passive"))
    )
    (net (code "102") (name "unconnected-(X2E-S-Pad13)") (class "Default")
      (node (ref "X2") (pin "13") (pinfunction "S_13") (pintype "passive"))
    )
    (net (code "103") (name "unconnected-(X2H-S-Pad16)") (class "Default")
      (node (ref "X2") (pin "16") (pinfunction "S_16") (pintype "passive"))
    )
    (net (code "104") (name "unconnected-(X2J-S-Pad18)") (class "Default")
      (node (ref "X2") (pin "18") (pinfunction "S_18") (pintype "passive"))
    )
    (net (code "105") (name "unconnected-(X2K-S-Pad19)") (class "Default")
      (node (ref "X2") (pin "19") (pinfunction "S_19") (pintype "passive"))
    )
    (net (code "106") (name "unconnected-(X2M-S-Pad20)") (class "Default")
      (node (ref "X2") (pin "20") (pinfunction "S_20") (pintype "passive"))
    )
    (net (code "107") (name "unconnected-(X2N-S-Pad21)") (class "Default")
      (node (ref "X2") (pin "21") (pinfunction "S_21") (pintype "passive"))
    )
    (net (code "108") (name "unconnected-(X2O-S-Pad22)") (class "Default")
      (node (ref "X2") (pin "22") (pinfunction "S_22") (pintype "passive"))
    )
    (net (code "109") (name "unconnected-(X2P-S-Pad23)") (class "Default")
      (node (ref "X2") (pin "23") (pinfunction "S_23") (pintype "passive"))
    )
    (net (code "110") (name "unconnected-(X2Q-S-Pad24)") (class "Default")
      (node (ref "X2") (pin "24") (pinfunction "S_24") (pintype "passive"))
    )
    (net (code "111") (name "unconnected-(X2T-S-Pad5)") (class "Default")
      (node (ref "X2") (pin "5") (pinfunction "S_5") (pintype "passive"))
    )
    (net (code "112") (name "unconnected-(X2U-S-Pad6)") (class "Default")
      (node (ref "X2") (pin "6") (pinfunction "S_6") (pintype "passive"))
    )
    (net (code "113") (name "unconnected-(X2V-S-Pad7)") (class "Default")
      (node (ref "X2") (pin "7") (pinfunction "S_7") (pintype "passive"))
    )
    (net (code "114") (name "unconnected-(X2W-S-Pad8)") (class "Default")
      (node (ref "X2") (pin "8") (pinfunction "S_8") (pintype "passive"))
    )
    (net (code "115") (name "unconnected-(X3D-S-Pad12)") (class "Default")
      (node (ref "X3") (pin "12") (pinfunction "S_12") (pintype "passive"))
    )
    (net (code "116") (name "unconnected-(X3E-S-Pad13)") (class "Default")
      (node (ref "X3") (pin "13") (pinfunction "S_13") (pintype "passive"))
    )
    (net (code "117") (name "unconnected-(X3H-S-Pad16)") (class "Default")
      (node (ref "X3") (pin "16") (pinfunction "S_16") (pintype "passive"))
    )
    (net (code "118") (name "unconnected-(X3J-S-Pad18)") (class "Default")
      (node (ref "X3") (pin "18") (pinfunction "S_18") (pintype "passive"))
    )
    (net (code "119") (name "unconnected-(X3K-S-Pad19)") (class "Default")
      (node (ref "X3") (pin "19") (pinfunction "S_19") (pintype "passive"))
    )
    (net (code "120") (name "unconnected-(X3M-S-Pad20)") (class "Default")
      (node (ref "X3") (pin "20") (pinfunction "S_20") (pintype "passive"))
    )
    (net (code "121") (name "unconnected-(X3N-S-Pad21)") (class "Default")
      (node (ref "X3") (pin "21") (pinfunction "S_21") (pintype "passive"))
    )
    (net (code "122") (name "unconnected-(X3O-S-Pad22)") (class "Default")
      (node (ref "X3") (pin "22") (pinfunction "S_22") (pintype "passive"))
    )
    (net (code "123") (name "unconnected-(X3P-S-Pad23)") (class "Default")
      (node (ref "X3") (pin "23") (pinfunction "S_23") (pintype "passive"))
    )
    (net (code "124") (name "unconnected-(X3Q-S-Pad24)") (class "Default")
      (node (ref "X3") (pin "24") (pinfunction "S_24") (pintype "passive"))
    )
    (net (code "125") (name "unconnected-(X3T-S-Pad5)") (class "Default")
      (node (ref "X3") (pin "5") (pinfunction "S_5") (pintype "passive"))
    )
    (net (code "126") (name "unconnected-(X3U-S-Pad6)") (class "Default")
      (node (ref "X3") (pin "6") (pinfunction "S_6") (pintype "passive"))
    )
    (net (code "127") (name "unconnected-(X3V-S-Pad7)") (class "Default")
      (node (ref "X3") (pin "7") (pinfunction "S_7") (pintype "passive"))
    )
    (net (code "128") (name "unconnected-(X3W-S-Pad8)") (class "Default")
      (node (ref "X3") (pin "8") (pinfunction "S_8") (pintype "passive"))
    )
  )
)
